# MainSch.net
KiCad netlist of a schematic drawn in Altium Designer
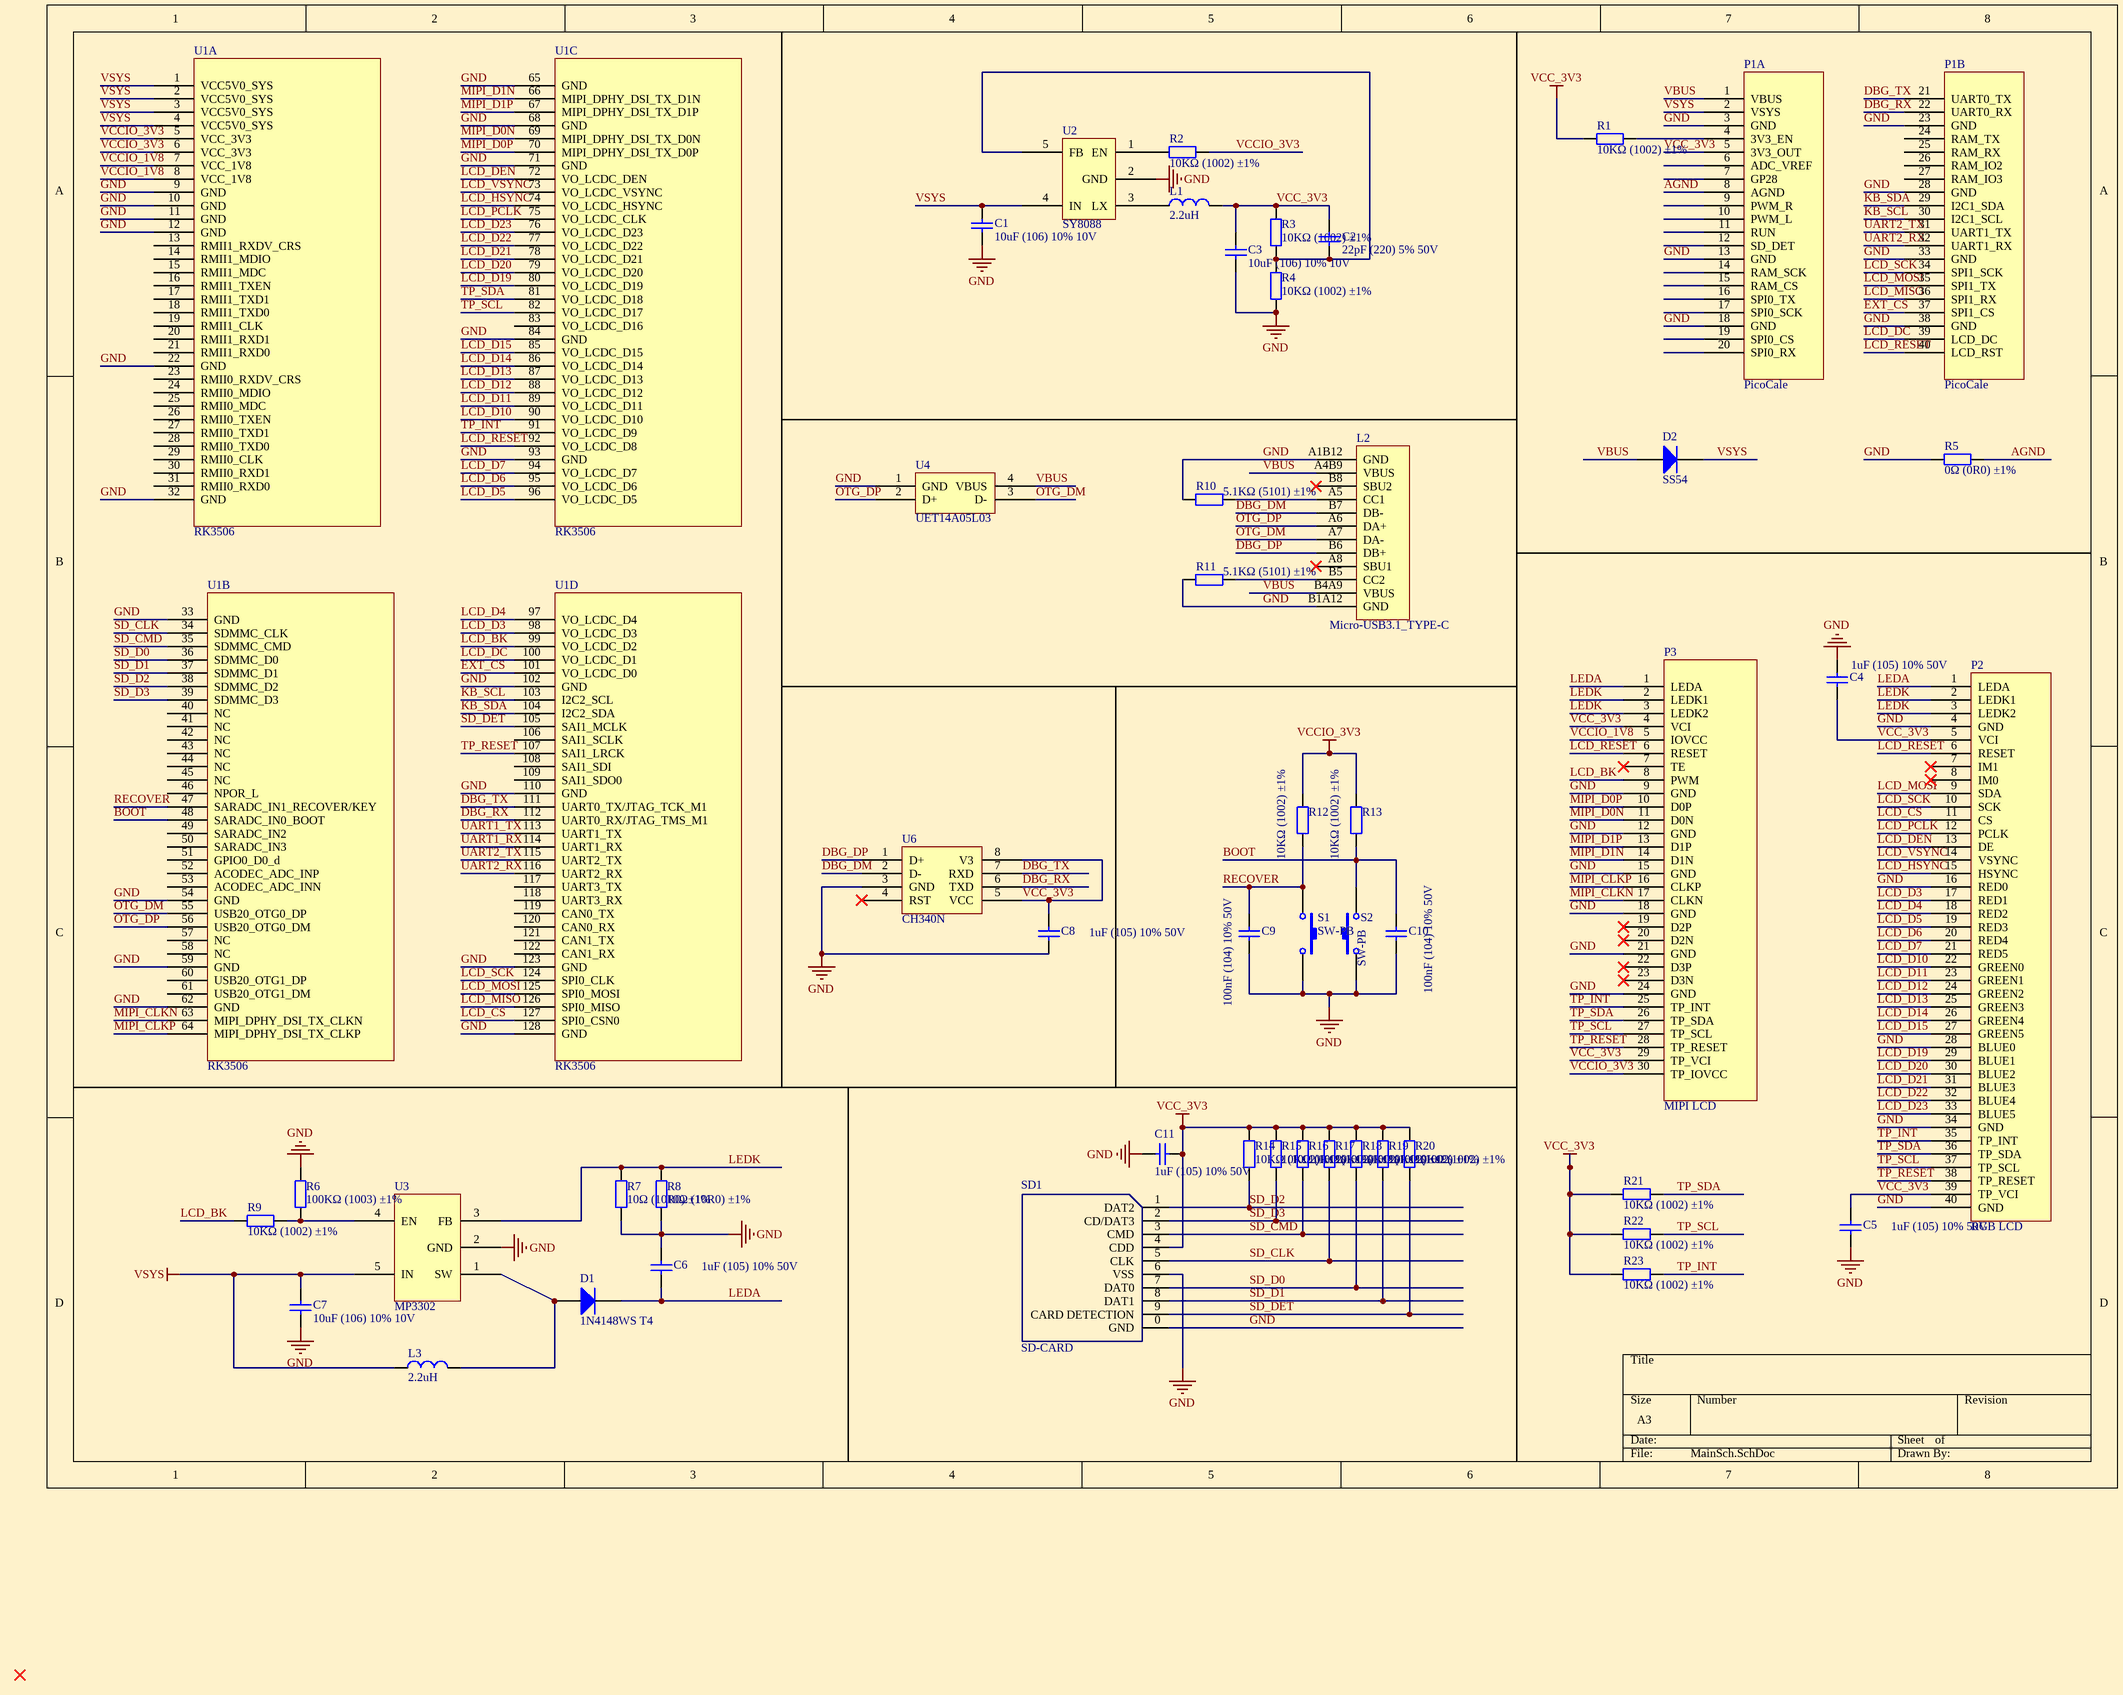
[diagram p0: MainSch.SchDoc]

(export (version "E")
  (design (tool "Eeschema 10.0.6"))
  (components
    (comp (ref "C1")
      (value "10uF (106) 10% 10V")
      (footprint "LC-0603_C")
      (description "贴片电容")
      (libsource (lib "Cap") (part "0603 10uF (106) 10% 10V"))
    )
    (comp (ref "C2")
      (value "22pF (220) 5% 50V")
      (footprint "LC-0603_C")
      (description "贴片电容")
      (libsource (lib "Cap") (part "0603 22pF (220) 5% 50V"))
    )
    (comp (ref "C3")
      (value "10uF (106) 10% 10V")
      (footprint "LC-0603_C")
      (description "贴片电容")
      (libsource (lib "Cap") (part "0603 10uF (106) 10% 10V"))
    )
    (comp (ref "C4")
      (value "1uF (105) 10% 50V")
      (footprint "LC-0603_C")
      (description "贴片电容")
      (libsource (lib "Cap") (part "0603 1uF (105) 10% 50V"))
    )
    (comp (ref "C5")
      (value "1uF (105) 10% 50V")
      (footprint "LC-0603_C")
      (description "贴片电容")
      (libsource (lib "Cap") (part "0603 1uF (105) 10% 50V"))
    )
    (comp (ref "C6")
      (value "1uF (105) 10% 50V")
      (footprint "LC-0603_C")
      (description "贴片电容")
      (libsource (lib "Cap") (part "0603 1uF (105) 10% 50V"))
    )
    (comp (ref "C7")
      (value "10uF (106) 10% 10V")
      (footprint "LC-0603_C")
      (description "贴片电容")
      (libsource (lib "Cap") (part "0603 10uF (106) 10% 10V"))
    )
    (comp (ref "C8")
      (value "1uF (105) 10% 50V")
      (footprint "LC-0603_C")
      (description "贴片电容")
      (libsource (lib "Cap") (part "0603 1uF (105) 10% 50V"))
    )
    (comp (ref "C9")
      (value "100nF (104) 10% 50V")
      (footprint "LC-0603_C")
      (description "贴片电容")
      (libsource (lib "Cap") (part "0603 100nF (104) 10% 50V"))
    )
    (comp (ref "C10")
      (value "100nF (104) 10% 50V")
      (footprint "LC-0603_C")
      (description "贴片电容")
      (libsource (lib "Cap") (part "0603 100nF (104) 10% 50V"))
    )
    (comp (ref "C11")
      (value "1uF (105) 10% 50V")
      (footprint "LC-0603_C")
      (description "贴片电容")
      (libsource (lib "Cap") (part "0603 1uF (105) 10% 50V"))
    )
    (comp (ref "D1")
      (value "1N4148WS T4")
      (footprint "LC-SOD-323")
      (description "二极管")
      (libsource (lib "Diode") (part "SOD-323 1N4148WS T4"))
    )
    (comp (ref "D2")
      (value "SS54")
      (footprint "LC-SMA(DO-214AC)_S1")
      (description "二极管")
      (libsource (lib "Diode") (part "SMA(DO-214AC) SS54"))
    )
    (comp (ref "L1")
      (value "2.2uH")
      (footprint "L-CD52")
      (description "电感")
      (libsource (lib "tony") (part "INDUCTOR"))
    )
    (comp (ref "L2")
      (value "Micro-USB3.1_TYPE-C")
      (footprint "USB_TypeC_SMD_16P")
      (libsource (lib "Miscellaneous Socket") (part "Micro-USB3.1_TYPE-C"))
    )
    (comp (ref "L3")
      (value "2.2uH")
      (footprint "L-CD52")
      (description "电感")
      (libsource (lib "tony") (part "INDUCTOR"))
    )
    (comp (ref "P1")
      (value "PicoCale")
      (footprint "Pico")
      (libsource (lib "rk3506_core") (part "PicoCale_Socket"))
    )
    (comp (ref "P2")
      (value "RGB LCD")
      (footprint "FPC0.5-40")
      (libsource (lib "rk3506_core") (part "RGB_40PIN"))
    )
    (comp (ref "P3")
      (value "MIPI LCD")
      (footprint "FPC0.5-30")
      (libsource (lib "rk3506_core") (part "MIPI_30P"))
    )
    (comp (ref "R1")
      (value "10KΩ (1002) ±1%")
      (footprint "LC-0603_R")
      (description "贴片电阻")
      (libsource (lib "") (part "0603 10KΩ (1002) 1%_2"))
    )
    (comp (ref "R2")
      (value "10KΩ (1002) ±1%")
      (footprint "LC-0603_R")
      (description "贴片电阻")
      (libsource (lib "") (part "0603 10KΩ (1002) 1%_2"))
    )
    (comp (ref "R3")
      (value "10KΩ (1002) ±1%")
      (footprint "LC-0603_R")
      (description "贴片电阻")
      (libsource (lib "RES") (part "0603 10KΩ (1002) 1%"))
    )
    (comp (ref "R4")
      (value "10KΩ (1002) ±1%")
      (footprint "LC-0603_R")
      (description "贴片电阻")
      (libsource (lib "RES") (part "0603 10KΩ (1002) 1%"))
    )
    (comp (ref "R5")
      (value "0Ω (0R0) ±1%")
      (footprint "LC-0603_R")
      (description "贴片电阻")
      (libsource (lib "RES") (part "0603 0Ω (0R0) 1%"))
    )
    (comp (ref "R6")
      (value "100KΩ (1003) ±1%")
      (footprint "LC-0603_R")
      (description "贴片电阻")
      (libsource (lib "RES") (part "0603 100KΩ (1003) 1%"))
    )
    (comp (ref "R7")
      (value "10Ω (10R0) ±1%")
      (footprint "LC-0603_R")
      (description "贴片电阻")
      (libsource (lib "RES") (part "0603 10Ω (10R0) 1%"))
    )
    (comp (ref "R8")
      (value "10Ω (10R0) ±1%")
      (footprint "LC-0603_R")
      (description "贴片电阻")
      (libsource (lib "RES") (part "0603 10Ω (10R0) 1%"))
    )
    (comp (ref "R9")
      (value "10KΩ (1002) ±1%")
      (footprint "LC-0603_R")
      (description "贴片电阻")
      (libsource (lib "") (part "0603 10KΩ (1002) 1%_2"))
    )
    (comp (ref "R10")
      (value "5.1KΩ (5101) ±1%")
      (footprint "LC-0603_R")
      (description "贴片电阻")
      (libsource (lib "RES") (part "0603 5.1KΩ (5101) 1%"))
    )
    (comp (ref "R11")
      (value "5.1KΩ (5101) ±1%")
      (footprint "LC-0603_R")
      (description "贴片电阻")
      (libsource (lib "RES") (part "0603 5.1KΩ (5101) 1%"))
    )
    (comp (ref "R12")
      (value "10KΩ (1002) ±1%")
      (footprint "LC-0603_R")
      (description "贴片电阻")
      (libsource (lib "RES") (part "0603 10KΩ (1002) 1%"))
    )
    (comp (ref "R13")
      (value "10KΩ (1002) ±1%")
      (footprint "LC-0603_R")
      (description "贴片电阻")
      (libsource (lib "RES") (part "0603 10KΩ (1002) 1%"))
    )
    (comp (ref "R14")
      (value "10KΩ (1002) ±1%")
      (footprint "LC-0603_R")
      (description "贴片电阻")
      (libsource (lib "RES") (part "0603 10KΩ (1002) 1%"))
    )
    (comp (ref "R15")
      (value "10KΩ (1002) ±1%")
      (footprint "LC-0603_R")
      (description "贴片电阻")
      (libsource (lib "RES") (part "0603 10KΩ (1002) 1%"))
    )
    (comp (ref "R16")
      (value "10KΩ (1002) ±1%")
      (footprint "LC-0603_R")
      (description "贴片电阻")
      (libsource (lib "RES") (part "0603 10KΩ (1002) 1%"))
    )
    (comp (ref "R17")
      (value "10KΩ (1002) ±1%")
      (footprint "LC-0603_R")
      (description "贴片电阻")
      (libsource (lib "RES") (part "0603 10KΩ (1002) 1%"))
    )
    (comp (ref "R18")
      (value "10KΩ (1002) ±1%")
      (footprint "LC-0603_R")
      (description "贴片电阻")
      (libsource (lib "RES") (part "0603 10KΩ (1002) 1%"))
    )
    (comp (ref "R19")
      (value "10KΩ (1002) ±1%")
      (footprint "LC-0603_R")
      (description "贴片电阻")
      (libsource (lib "RES") (part "0603 10KΩ (1002) 1%"))
    )
    (comp (ref "R20")
      (value "10KΩ (1002) ±1%")
      (footprint "LC-0603_R")
      (description "贴片电阻")
      (libsource (lib "RES") (part "0603 10KΩ (1002) 1%"))
    )
    (comp (ref "R21")
      (value "10KΩ (1002) ±1%")
      (footprint "LC-0603_R")
      (description "贴片电阻")
      (libsource (lib "") (part "0603 10KΩ (1002) 1%_1"))
    )
    (comp (ref "R22")
      (value "10KΩ (1002) ±1%")
      (footprint "LC-0603_R")
      (description "贴片电阻")
      (libsource (lib "") (part "0603 10KΩ (1002) 1%_1"))
    )
    (comp (ref "R23")
      (value "10KΩ (1002) ±1%")
      (footprint "LC-0603_R")
      (description "贴片电阻")
      (libsource (lib "") (part "0603 10KΩ (1002) 1%_1"))
    )
    (comp (ref "S1")
      (value "SW-PB")
      (footprint "TS-1030")
      (description "轻触开关")
      (fields (field (name "PUBLISHER") "Altium Limited"))
      (libsource (lib "tony") (part "SW-PB"))
    )
    (comp (ref "S2")
      (value "SW-PB")
      (footprint "TS-1030")
      (description "轻触开关")
      (fields (field (name "PUBLISHER") "Altium Limited"))
      (libsource (lib "tony") (part "SW-PB"))
    )
    (comp (ref "SD1")
      (value "SD-CARD")
      (footprint "SD-CARD-Micro")
      (libsource (lib "Miscellaneous Socket") (part "SD-CARD"))
    )
    (comp (ref "U1")
      (value "RK3506")
      (footprint "RK3506")
      (libsource (lib "rk3506_core") (part "RK3506G_CORE"))
    )
    (comp (ref "U2") (value "SY8088") (footprint "SOT23-5") (libsource (lib "rk3506_core") (part "SY8088")))
    (comp (ref "U3") (value "MP3302") (footprint "SOT23-5") (libsource (lib "rk3506_core") (part "MP3302")))
    (comp (ref "U4")
      (value "UET14A05L03")
      (footprint "SOT-143")
      (libsource (lib "rk3506_core") (part "UET14A05L03"))
    )
    (comp (ref "U6") (value "CH340N") (footprint "SOP8") (libsource (lib "rk3506_core") (part "CH340N")))
  )
  (nets
    (net (code "1") (name "/AGND") (class "Default")
      (node (ref "P1") (pin "8") (pinfunction "AGND_8") (pintype "passive"))
      (node (ref "R5") (pin "2") (pinfunction "2_2") (pintype "passive"))
    )
    (net (code "2") (name "/BOOT") (class "Default")
      (node (ref "C10") (pin "2") (pinfunction "2_2") (pintype "passive"))
      (node (ref "R13") (pin "1") (pinfunction "1_1") (pintype "passive"))
      (node (ref "S2") (pin "2") (pinfunction "2_2") (pintype "passive"))
      (node (ref "U1") (pin "48") (pinfunction "SARADC_IN0_BOOT_48") (pintype "passive"))
    )
    (net (code "3") (name "/DBG_DM") (class "Default")
      (node (ref "L2") (pin "B7") (pinfunction "DB-_B7") (pintype "passive"))
      (node (ref "U6") (pin "2") (pinfunction "D-_2") (pintype "passive"))
    )
    (net (code "4") (name "/DBG_DP") (class "Default")
      (node (ref "L2") (pin "B6") (pinfunction "DB+_B6") (pintype "passive"))
      (node (ref "U6") (pin "1") (pinfunction "D+_1") (pintype "passive"))
    )
    (net (code "5") (name "/DBG_RX") (class "Default")
      (node (ref "P1") (pin "22") (pinfunction "UART0_RX_22") (pintype "passive"))
      (node (ref "U1") (pin "112") (pinfunction "UART0_RX/JTAG_TMS_M1_112") (pintype "passive"))
      (node (ref "U6") (pin "6") (pinfunction "TXD_6") (pintype "passive"))
    )
    (net (code "6") (name "/DBG_TX") (class "Default")
      (node (ref "P1") (pin "21") (pinfunction "UART0_TX_21") (pintype "passive"))
      (node (ref "U1") (pin "111") (pinfunction "UART0_TX/JTAG_TCK_M1_111") (pintype "passive"))
      (node (ref "U6") (pin "7") (pinfunction "RXD_7") (pintype "passive"))
    )
    (net (code "7") (name "/EXT_CS") (class "Default")
      (node (ref "P1") (pin "37") (pinfunction "SPI1_CS_37") (pintype "passive"))
      (node (ref "U1") (pin "101") (pinfunction "VO_LCDC_D0_101") (pintype "passive"))
    )
    (net (code "8") (name "/KB_SCL") (class "Default")
      (node (ref "P1") (pin "30") (pinfunction "I2C1_SCL_30") (pintype "passive"))
      (node (ref "U1") (pin "103") (pinfunction "I2C2_SCL_103") (pintype "passive"))
    )
    (net (code "9") (name "/KB_SDA") (class "Default")
      (node (ref "P1") (pin "29") (pinfunction "I2C1_SDA_29") (pintype "passive"))
      (node (ref "U1") (pin "104") (pinfunction "I2C2_SDA_104") (pintype "passive"))
    )
    (net (code "10") (name "/LCD_BK") (class "Default")
      (node (ref "P3") (pin "8") (pinfunction "PWM_8") (pintype "passive"))
      (node (ref "R9") (pin "1") (pinfunction "1_1") (pintype "passive"))
      (node (ref "U1") (pin "99") (pinfunction "VO_LCDC_D2_99") (pintype "passive"))
    )
    (net (code "11") (name "/LCD_CS") (class "Default")
      (node (ref "P2") (pin "11") (pinfunction "CS_11") (pintype "passive"))
      (node (ref "U1") (pin "127") (pinfunction "SPI0_CSN0_127") (pintype "passive"))
    )
    (net (code "12") (name "/LCD_D3") (class "Default")
      (node (ref "P2") (pin "17") (pinfunction "RED1_17") (pintype "passive"))
      (node (ref "U1") (pin "98") (pinfunction "VO_LCDC_D3_98") (pintype "passive"))
    )
    (net (code "13") (name "/LCD_D4") (class "Default")
      (node (ref "P2") (pin "18") (pinfunction "RED2_18") (pintype "passive"))
      (node (ref "U1") (pin "97") (pinfunction "VO_LCDC_D4_97") (pintype "passive"))
    )
    (net (code "14") (name "/LCD_D5") (class "Default")
      (node (ref "P2") (pin "19") (pinfunction "RED3_19") (pintype "passive"))
      (node (ref "U1") (pin "96") (pinfunction "VO_LCDC_D5_96") (pintype "passive"))
    )
    (net (code "15") (name "/LCD_D6") (class "Default")
      (node (ref "P2") (pin "20") (pinfunction "RED4_20") (pintype "passive"))
      (node (ref "U1") (pin "95") (pinfunction "VO_LCDC_D6_95") (pintype "passive"))
    )
    (net (code "16") (name "/LCD_D7") (class "Default")
      (node (ref "P2") (pin "21") (pinfunction "RED5_21") (pintype "passive"))
      (node (ref "U1") (pin "94") (pinfunction "VO_LCDC_D7_94") (pintype "passive"))
    )
    (net (code "17") (name "/LCD_D10") (class "Default")
      (node (ref "P2") (pin "22") (pinfunction "GREEN0_22") (pintype "passive"))
      (node (ref "U1") (pin "90") (pinfunction "VO_LCDC_D10_90") (pintype "passive"))
    )
    (net (code "18") (name "/LCD_D11") (class "Default")
      (node (ref "P2") (pin "23") (pinfunction "GREEN1_23") (pintype "passive"))
      (node (ref "U1") (pin "89") (pinfunction "VO_LCDC_D11_89") (pintype "passive"))
    )
    (net (code "19") (name "/LCD_D12") (class "Default")
      (node (ref "P2") (pin "24") (pinfunction "GREEN2_24") (pintype "passive"))
      (node (ref "U1") (pin "88") (pinfunction "VO_LCDC_D12_88") (pintype "passive"))
    )
    (net (code "20") (name "/LCD_D13") (class "Default")
      (node (ref "P2") (pin "25") (pinfunction "GREEN3_25") (pintype "passive"))
      (node (ref "U1") (pin "87") (pinfunction "VO_LCDC_D13_87") (pintype "passive"))
    )
    (net (code "21") (name "/LCD_D14") (class "Default")
      (node (ref "P2") (pin "26") (pinfunction "GREEN4_26") (pintype "passive"))
      (node (ref "U1") (pin "86") (pinfunction "VO_LCDC_D14_86") (pintype "passive"))
    )
    (net (code "22") (name "/LCD_D15") (class "Default")
      (node (ref "P2") (pin "27") (pinfunction "GREEN5_27") (pintype "passive"))
      (node (ref "U1") (pin "85") (pinfunction "VO_LCDC_D15_85") (pintype "passive"))
    )
    (net (code "23") (name "/LCD_D19") (class "Default")
      (node (ref "P2") (pin "29") (pinfunction "BLUE1_29") (pintype "passive"))
      (node (ref "U1") (pin "80") (pinfunction "VO_LCDC_D19_80") (pintype "passive"))
    )
    (net (code "24") (name "/LCD_D20") (class "Default")
      (node (ref "P2") (pin "30") (pinfunction "BLUE2_30") (pintype "passive"))
      (node (ref "U1") (pin "79") (pinfunction "VO_LCDC_D20_79") (pintype "passive"))
    )
    (net (code "25") (name "/LCD_D21") (class "Default")
      (node (ref "P2") (pin "31") (pinfunction "BLUE3_31") (pintype "passive"))
      (node (ref "U1") (pin "78") (pinfunction "VO_LCDC_D21_78") (pintype "passive"))
    )
    (net (code "26") (name "/LCD_D22") (class "Default")
      (node (ref "P2") (pin "32") (pinfunction "BLUE4_32") (pintype "passive"))
      (node (ref "U1") (pin "77") (pinfunction "VO_LCDC_D22_77") (pintype "passive"))
    )
    (net (code "27") (name "/LCD_D23") (class "Default")
      (node (ref "P2") (pin "33") (pinfunction "BLUE5_33") (pintype "passive"))
      (node (ref "U1") (pin "76") (pinfunction "VO_LCDC_D23_76") (pintype "passive"))
    )
    (net (code "28") (name "/LCD_DC") (class "Default")
      (node (ref "P1") (pin "39") (pinfunction "LCD_DC_39") (pintype "passive"))
      (node (ref "U1") (pin "100") (pinfunction "VO_LCDC_D1_100") (pintype "passive"))
    )
    (net (code "29") (name "/LCD_DEN") (class "Default")
      (node (ref "P2") (pin "13") (pinfunction "DE_13") (pintype "passive"))
      (node (ref "U1") (pin "72") (pinfunction "VO_LCDC_DEN_72") (pintype "passive"))
    )
    (net (code "30") (name "/LCD_HSYNC") (class "Default")
      (node (ref "P2") (pin "15") (pinfunction "HSYNC_15") (pintype "passive"))
      (node (ref "U1") (pin "74") (pinfunction "VO_LCDC_HSYNC_74") (pintype "passive"))
    )
    (net (code "31") (name "/LCD_MISO") (class "Default")
      (node (ref "P1") (pin "36") (pinfunction "SPI1_RX_36") (pintype "passive"))
      (node (ref "U1") (pin "126") (pinfunction "SPI0_MISO_126") (pintype "passive"))
    )
    (net (code "32") (name "/LCD_MOSI") (class "Default")
      (node (ref "P1") (pin "35") (pinfunction "SPI1_TX_35") (pintype "passive"))
      (node (ref "P2") (pin "9") (pinfunction "SDA_9") (pintype "passive"))
      (node (ref "U1") (pin "125") (pinfunction "SPI0_MOSI_125") (pintype "passive"))
    )
    (net (code "33") (name "/LCD_PCLK") (class "Default")
      (node (ref "P2") (pin "12") (pinfunction "PCLK_12") (pintype "passive"))
      (node (ref "U1") (pin "75") (pinfunction "VO_LCDC_CLK_75") (pintype "passive"))
    )
    (net (code "34") (name "/LCD_RESET") (class "Default")
      (node (ref "P1") (pin "40") (pinfunction "LCD_RST_40") (pintype "passive"))
      (node (ref "P2") (pin "6") (pinfunction "RESET_6") (pintype "passive"))
      (node (ref "P3") (pin "6") (pinfunction "RESET_6") (pintype "passive"))
      (node (ref "U1") (pin "92") (pinfunction "VO_LCDC_D8_92") (pintype "passive"))
    )
    (net (code "35") (name "/LCD_SCK") (class "Default")
      (node (ref "P1") (pin "34") (pinfunction "SPI1_SCK_34") (pintype "passive"))
      (node (ref "P2") (pin "10") (pinfunction "SCK_10") (pintype "passive"))
      (node (ref "U1") (pin "124") (pinfunction "SPI0_CLK_124") (pintype "passive"))
    )
    (net (code "36") (name "/LCD_VSYNC") (class "Default")
      (node (ref "P2") (pin "14") (pinfunction "VSYNC_14") (pintype "passive"))
      (node (ref "U1") (pin "73") (pinfunction "VO_LCDC_VSYNC_73") (pintype "passive"))
    )
    (net (code "37") (name "/LEDA") (class "Default")
      (node (ref "C6") (pin "1") (pinfunction "1_1") (pintype "passive"))
      (node (ref "D1") (pin "2") (pinfunction "K_2") (pintype "passive"))
      (node (ref "P2") (pin "1") (pinfunction "LEDA_1") (pintype "passive"))
      (node (ref "P3") (pin "1") (pinfunction "LEDA_1") (pintype "passive"))
    )
    (net (code "38") (name "/LEDK") (class "Default")
      (node (ref "P2") (pin "2") (pinfunction "LEDK1_2") (pintype "passive"))
      (node (ref "P2") (pin "3") (pinfunction "LEDK2_3") (pintype "passive"))
      (node (ref "P3") (pin "2") (pinfunction "LEDK1_2") (pintype "passive"))
      (node (ref "P3") (pin "3") (pinfunction "LEDK2_3") (pintype "passive"))
      (node (ref "R7") (pin "2") (pinfunction "2_2") (pintype "passive"))
      (node (ref "R8") (pin "2") (pinfunction "2_2") (pintype "passive"))
      (node (ref "U3") (pin "3") (pinfunction "FB_3") (pintype "passive"))
    )
    (net (code "39") (name "/MIPI_CLKN") (class "Default")
      (node (ref "P3") (pin "17") (pinfunction "CLKN_17") (pintype "passive"))
      (node (ref "U1") (pin "63") (pinfunction "MIPI_DPHY_DSI_TX_CLKN_63") (pintype "passive"))
    )
    (net (code "40") (name "/MIPI_CLKP") (class "Default")
      (node (ref "P3") (pin "16") (pinfunction "CLKP_16") (pintype "passive"))
      (node (ref "U1") (pin "64") (pinfunction "MIPI_DPHY_DSI_TX_CLKP_64") (pintype "passive"))
    )
    (net (code "41") (name "/MIPI_D0N") (class "Default")
      (node (ref "P3") (pin "11") (pinfunction "D0N_11") (pintype "passive"))
      (node (ref "U1") (pin "69") (pinfunction "MIPI_DPHY_DSI_TX_D0N_69") (pintype "passive"))
    )
    (net (code "42") (name "/MIPI_D0P") (class "Default")
      (node (ref "P3") (pin "10") (pinfunction "D0P_10") (pintype "passive"))
      (node (ref "U1") (pin "70") (pinfunction "MIPI_DPHY_DSI_TX_D0P_70") (pintype "passive"))
    )
    (net (code "43") (name "/MIPI_D1N") (class "Default")
      (node (ref "P3") (pin "14") (pinfunction "D1N_14") (pintype "passive"))
      (node (ref "U1") (pin "66") (pinfunction "MIPI_DPHY_DSI_TX_D1N_66") (pintype "passive"))
    )
    (net (code "44") (name "/MIPI_D1P") (class "Default")
      (node (ref "P3") (pin "13") (pinfunction "D1P_13") (pintype "passive"))
      (node (ref "U1") (pin "67") (pinfunction "MIPI_DPHY_DSI_TX_D1P_67") (pintype "passive"))
    )
    (net (code "45") (name "/OTG_DM") (class "Default")
      (node (ref "L2") (pin "A7") (pinfunction "DA-_A7") (pintype "passive"))
      (node (ref "U1") (pin "55") (pinfunction "USB20_OTG0_DP_55") (pintype "passive"))
      (node (ref "U4") (pin "3") (pinfunction "D-_3") (pintype "passive"))
    )
    (net (code "46") (name "/OTG_DP") (class "Default")
      (node (ref "L2") (pin "A6") (pinfunction "DA+_A6") (pintype "passive"))
      (node (ref "U1") (pin "56") (pinfunction "USB20_OTG0_DM_56") (pintype "passive"))
      (node (ref "U4") (pin "2") (pinfunction "D+_2") (pintype "passive"))
    )
    (net (code "47") (name "/RECOVER") (class "Default")
      (node (ref "C9") (pin "2") (pinfunction "2_2") (pintype "passive"))
      (node (ref "R12") (pin "1") (pinfunction "1_1") (pintype "passive"))
      (node (ref "S1") (pin "1") (pinfunction "1_1") (pintype "passive"))
      (node (ref "U1") (pin "47") (pinfunction "SARADC_IN1_RECOVER/KEY_47") (pintype "passive"))
    )
    (net (code "48") (name "/SD_CLK") (class "Default")
      (node (ref "R17") (pin "1") (pinfunction "1_1") (pintype "passive"))
      (node (ref "SD1") (pin "5") (pinfunction "CLK_5") (pintype "passive"))
      (node (ref "U1") (pin "34") (pinfunction "SDMMC_CLK_34") (pintype "passive"))
    )
    (net (code "49") (name "/SD_CMD") (class "Default")
      (node (ref "R16") (pin "1") (pinfunction "1_1") (pintype "passive"))
      (node (ref "SD1") (pin "3") (pinfunction "CMD_3") (pintype "passive"))
      (node (ref "U1") (pin "35") (pinfunction "SDMMC_CMD_35") (pintype "passive"))
    )
    (net (code "50") (name "/SD_D0") (class "Default")
      (node (ref "R18") (pin "1") (pinfunction "1_1") (pintype "passive"))
      (node (ref "SD1") (pin "7") (pinfunction "DAT0_7") (pintype "passive"))
      (node (ref "U1") (pin "36") (pinfunction "SDMMC_D0_36") (pintype "passive"))
    )
    (net (code "51") (name "/SD_D1") (class "Default")
      (node (ref "R19") (pin "1") (pinfunction "1_1") (pintype "passive"))
      (node (ref "SD1") (pin "8") (pinfunction "DAT1_8") (pintype "passive"))
      (node (ref "U1") (pin "37") (pinfunction "SDMMC_D1_37") (pintype "passive"))
    )
    (net (code "52") (name "/SD_D2") (class "Default")
      (node (ref "R14") (pin "1") (pinfunction "1_1") (pintype "passive"))
      (node (ref "SD1") (pin "1") (pinfunction "DAT2_1") (pintype "passive"))
      (node (ref "U1") (pin "38") (pinfunction "SDMMC_D2_38") (pintype "passive"))
    )
    (net (code "53") (name "/SD_D3") (class "Default")
      (node (ref "R15") (pin "1") (pinfunction "1_1") (pintype "passive"))
      (node (ref "SD1") (pin "2") (pinfunction "CD/DAT3_2") (pintype "passive"))
      (node (ref "U1") (pin "39") (pinfunction "SDMMC_D3_39") (pintype "passive"))
    )
    (net (code "54") (name "/SD_DET") (class "Default")
      (node (ref "R20") (pin "1") (pinfunction "1_1") (pintype "passive"))
      (node (ref "SD1") (pin "9") (pinfunction "CARD_DETECTION_9") (pintype "passive"))
      (node (ref "U1") (pin "105") (pinfunction "SAI1_MCLK_105") (pintype "passive"))
    )
    (net (code "55") (name "/TP_INT") (class "Default")
      (node (ref "P2") (pin "35") (pinfunction "TP_INT_35") (pintype "passive"))
      (node (ref "P3") (pin "25") (pinfunction "TP_INT_25") (pintype "passive"))
      (node (ref "R23") (pin "1") (pinfunction "1_1") (pintype "passive"))
      (node (ref "U1") (pin "91") (pinfunction "VO_LCDC_D9_91") (pintype "passive"))
    )
    (net (code "56") (name "/TP_RESET") (class "Default")
      (node (ref "P2") (pin "38") (pinfunction "TP_RESET_38") (pintype "passive"))
      (node (ref "P3") (pin "28") (pinfunction "TP_RESET_28") (pintype "passive"))
      (node (ref "U1") (pin "107") (pinfunction "SAI1_LRCK_107") (pintype "passive"))
    )
    (net (code "57") (name "/TP_SCL") (class "Default")
      (node (ref "P2") (pin "37") (pinfunction "TP_SCL_37") (pintype "passive"))
      (node (ref "P3") (pin "27") (pinfunction "TP_SCL_27") (pintype "passive"))
      (node (ref "R22") (pin "1") (pinfunction "1_1") (pintype "passive"))
      (node (ref "U1") (pin "82") (pinfunction "VO_LCDC_D17_82") (pintype "passive"))
    )
    (net (code "58") (name "/TP_SDA") (class "Default")
      (node (ref "P2") (pin "36") (pinfunction "TP_SDA_36") (pintype "passive"))
      (node (ref "P3") (pin "26") (pinfunction "TP_SDA_26") (pintype "passive"))
      (node (ref "R21") (pin "1") (pinfunction "1_1") (pintype "passive"))
      (node (ref "U1") (pin "81") (pinfunction "VO_LCDC_D18_81") (pintype "passive"))
    )
    (net (code "59") (name "/UART1_RX") (class "Default")
      (node (ref "U1") (pin "114") (pinfunction "UART1_RX_114") (pintype "passive"))
    )
    (net (code "60") (name "/UART1_TX") (class "Default")
      (node (ref "U1") (pin "113") (pinfunction "UART1_TX_113") (pintype "passive"))
    )
    (net (code "61") (name "/UART2_RX") (class "Default")
      (node (ref "P1") (pin "32") (pinfunction "UART1_RX_32") (pintype "passive"))
      (node (ref "U1") (pin "116") (pinfunction "UART2_RX_116") (pintype "passive"))
    )
    (net (code "62") (name "/UART2_TX") (class "Default")
      (node (ref "P1") (pin "31") (pinfunction "UART1_TX_31") (pintype "passive"))
      (node (ref "U1") (pin "115") (pinfunction "UART2_TX_115") (pintype "passive"))
    )
    (net (code "63") (name "/VBUS") (class "Default")
      (node (ref "D2") (pin "1") (pinfunction "A_1") (pintype "passive"))
      (node (ref "L2") (pin "A4B9") (pinfunction "VBUS_A4B9") (pintype "passive"))
      (node (ref "L2") (pin "B4A9") (pinfunction "VBUS_B4A9") (pintype "passive"))
      (node (ref "P1") (pin "1") (pinfunction "VBUS_1") (pintype "passive"))
      (node (ref "U4") (pin "4") (pinfunction "VBUS_4") (pintype "passive"))
    )
    (net (code "64") (name "/VCCIO_1V8") (class "Default")
      (node (ref "P3") (pin "5") (pinfunction "IOVCC_5") (pintype "passive"))
      (node (ref "U1") (pin "7") (pinfunction "VCC_1V8_7") (pintype "passive"))
      (node (ref "U1") (pin "8") (pinfunction "VCC_1V8_8") (pintype "passive"))
    )
    (net (code "65") (name "GND") (class "Default")
      (node (ref "C1") (pin "1") (pinfunction "1_1") (pintype "passive"))
      (node (ref "C10") (pin "1") (pinfunction "1_1") (pintype "passive"))
      (node (ref "C11") (pin "2") (pinfunction "2_2") (pintype "passive"))
      (node (ref "C3") (pin "1") (pinfunction "1_1") (pintype "passive"))
      (node (ref "C4") (pin "1") (pinfunction "1_1") (pintype "passive"))
      (node (ref "C5") (pin "1") (pinfunction "1_1") (pintype "passive"))
      (node (ref "C6") (pin "2") (pinfunction "2_2") (pintype "passive"))
      (node (ref "C7") (pin "1") (pinfunction "1_1") (pintype "passive"))
      (node (ref "C8") (pin "1") (pinfunction "1_1") (pintype "passive"))
      (node (ref "C9") (pin "1") (pinfunction "1_1") (pintype "passive"))
      (node (ref "L2") (pin "A1B12") (pinfunction "GND_A1B12") (pintype "passive"))
      (node (ref "L2") (pin "B1A12") (pinfunction "GND_B1A12") (pintype "passive"))
      (node (ref "P1") (pin "13") (pinfunction "GND_13") (pintype "passive"))
      (node (ref "P1") (pin "18") (pinfunction "GND_18") (pintype "passive"))
      (node (ref "P1") (pin "23") (pinfunction "GND_23") (pintype "passive"))
      (node (ref "P1") (pin "28") (pinfunction "GND_28") (pintype "passive"))
      (node (ref "P1") (pin "3") (pinfunction "GND_3") (pintype "passive"))
      (node (ref "P1") (pin "33") (pinfunction "GND_33") (pintype "passive"))
      (node (ref "P1") (pin "38") (pinfunction "GND_38") (pintype "passive"))
      (node (ref "P2") (pin "16") (pinfunction "RED0_16") (pintype "passive"))
      (node (ref "P2") (pin "28") (pinfunction "BLUE0_28") (pintype "passive"))
      (node (ref "P2") (pin "34") (pinfunction "GND_34") (pintype "passive"))
      (node (ref "P2") (pin "4") (pinfunction "GND_4") (pintype "passive"))
      (node (ref "P2") (pin "40") (pinfunction "GND_40") (pintype "passive"))
      (node (ref "P3") (pin "12") (pinfunction "GND_12") (pintype "passive"))
      (node (ref "P3") (pin "15") (pinfunction "GND_15") (pintype "passive"))
      (node (ref "P3") (pin "18") (pinfunction "GND_18") (pintype "passive"))
      (node (ref "P3") (pin "21") (pinfunction "GND_21") (pintype "passive"))
      (node (ref "P3") (pin "24") (pinfunction "GND_24") (pintype "passive"))
      (node (ref "P3") (pin "9") (pinfunction "GND_9") (pintype "passive"))
      (node (ref "R10") (pin "1") (pinfunction "1_1") (pintype "passive"))
      (node (ref "R11") (pin "1") (pinfunction "1_1") (pintype "passive"))
      (node (ref "R4") (pin "1") (pinfunction "1_1") (pintype "passive"))
      (node (ref "R5") (pin "1") (pinfunction "1_1") (pintype "passive"))
      (node (ref "R6") (pin "2") (pinfunction "2_2") (pintype "passive"))
      (node (ref "R7") (pin "1") (pinfunction "1_1") (pintype "passive"))
      (node (ref "R8") (pin "1") (pinfunction "1_1") (pintype "passive"))
      (node (ref "S1") (pin "2") (pinfunction "2_2") (pintype "passive"))
      (node (ref "S2") (pin "1") (pinfunction "1_1") (pintype "passive"))
      (node (ref "SD1") (pin "0") (pinfunction "GND_0") (pintype "passive"))
      (node (ref "SD1") (pin "6") (pinfunction "VSS_6") (pintype "passive"))
      (node (ref "U1") (pin "10") (pinfunction "GND_10") (pintype "passive"))
      (node (ref "U1") (pin "102") (pinfunction "GND_102") (pintype "passive"))
      (node (ref "U1") (pin "11") (pinfunction "GND_11") (pintype "passive"))
      (node (ref "U1") (pin "110") (pinfunction "GND_110") (pintype "passive"))
      (node (ref "U1") (pin "12") (pinfunction "GND_12") (pintype "passive"))
      (node (ref "U1") (pin "123") (pinfunction "GND_123") (pintype "passive"))
      (node (ref "U1") (pin "128") (pinfunction "GND_128") (pintype "passive"))
      (node (ref "U1") (pin "22") (pinfunction "GND_22") (pintype "passive"))
      (node (ref "U1") (pin "32") (pinfunction "GND_32") (pintype "passive"))
      (node (ref "U1") (pin "33") (pinfunction "GND_33") (pintype "passive"))
      (node (ref "U1") (pin "54") (pinfunction "GND_54") (pintype "passive"))
      (node (ref "U1") (pin "59") (pinfunction "GND_59") (pintype "passive"))
      (node (ref "U1") (pin "62") (pinfunction "GND_62") (pintype "passive"))
      (node (ref "U1") (pin "65") (pinfunction "GND_65") (pintype "passive"))
      (node (ref "U1") (pin "68") (pinfunction "GND_68") (pintype "passive"))
      (node (ref "U1") (pin "71") (pinfunction "GND_71") (pintype "passive"))
      (node (ref "U1") (pin "84") (pinfunction "GND_84") (pintype "passive"))
      (node (ref "U1") (pin "9") (pinfunction "GND_9") (pintype "passive"))
      (node (ref "U1") (pin "93") (pinfunction "GND_93") (pintype "passive"))
      (node (ref "U2") (pin "2") (pinfunction "GND_2") (pintype "passive"))
      (node (ref "U3") (pin "2") (pinfunction "GND_2") (pintype "passive"))
      (node (ref "U4") (pin "1") (pinfunction "GND_1") (pintype "passive"))
      (node (ref "U6") (pin "3") (pinfunction "GND_3") (pintype "passive"))
    )
    (net (code "66") (name "Net-(D1-A)") (class "Default")
      (node (ref "D1") (pin "1") (pinfunction "A_1") (pintype "passive"))
      (node (ref "L3") (pin "1") (pinfunction "1_1") (pintype "passive"))
      (node (ref "U3") (pin "1") (pinfunction "SW_1") (pintype "passive"))
    )
    (net (code "67") (name "Net-(L2-CC1)") (class "Default")
      (node (ref "L2") (pin "A5") (pinfunction "CC1_A5") (pintype "passive"))
      (node (ref "R10") (pin "2") (pinfunction "2_2") (pintype "passive"))
    )
    (net (code "68") (name "Net-(L2-CC2)") (class "Default")
      (node (ref "L2") (pin "B5") (pinfunction "CC2_B5") (pintype "passive"))
      (node (ref "R11") (pin "2") (pinfunction "2_2") (pintype "passive"))
    )
    (net (code "69") (name "Net-(P1A-3V3_EN)") (class "Default")
      (node (ref "P1") (pin "4") (pinfunction "3V3_EN_4") (pintype "passive"))
      (node (ref "R1") (pin "2") (pinfunction "2_2") (pintype "passive"))
    )
    (net (code "70") (name "Net-(U2-EN)") (class "Default")
      (node (ref "R2") (pin "1") (pinfunction "1_1") (pintype "passive"))
      (node (ref "U2") (pin "1") (pinfunction "EN_1") (pintype "passive"))
    )
    (net (code "71") (name "Net-(U2-FB)") (class "Default")
      (node (ref "C2") (pin "1") (pinfunction "1_1") (pintype "passive"))
      (node (ref "R3") (pin "1") (pinfunction "1_1") (pintype "passive"))
      (node (ref "R4") (pin "2") (pinfunction "2_2") (pintype "passive"))
      (node (ref "U2") (pin "5") (pinfunction "FB_5") (pintype "passive"))
    )
    (net (code "72") (name "Net-(U2-LX)") (class "Default")
      (node (ref "L1") (pin "2") (pinfunction "2_2") (pintype "passive"))
      (node (ref "U2") (pin "3") (pinfunction "LX_3") (pintype "passive"))
    )
    (net (code "73") (name "Net-(U3-EN)") (class "Default")
      (node (ref "R6") (pin "1") (pinfunction "1_1") (pintype "passive"))
      (node (ref "R9") (pin "2") (pinfunction "2_2") (pintype "passive"))
      (node (ref "U3") (pin "4") (pinfunction "EN_4") (pintype "passive"))
    )
    (net (code "74") (name "VCCIO_3V3") (class "Default")
      (node (ref "P3") (pin "30") (pinfunction "TP_IOVCC_30") (pintype "passive"))
      (node (ref "R12") (pin "2") (pinfunction "2_2") (pintype "passive"))
      (node (ref "R13") (pin "2") (pinfunction "2_2") (pintype "passive"))
      (node (ref "R2") (pin "2") (pinfunction "2_2") (pintype "passive"))
      (node (ref "U1") (pin "5") (pinfunction "VCC_3V3_5") (pintype "passive"))
      (node (ref "U1") (pin "6") (pinfunction "VCC_3V3_6") (pintype "passive"))
    )
    (net (code "75") (name "VCC_3V3") (class "Default")
      (node (ref "C11") (pin "1") (pinfunction "1_1") (pintype "passive"))
      (node (ref "C2") (pin "2") (pinfunction "2_2") (pintype "passive"))
      (node (ref "C3") (pin "2") (pinfunction "2_2") (pintype "passive"))
      (node (ref "C4") (pin "2") (pinfunction "2_2") (pintype "passive"))
      (node (ref "C5") (pin "2") (pinfunction "2_2") (pintype "passive"))
      (node (ref "C8") (pin "2") (pinfunction "2_2") (pintype "passive"))
      (node (ref "L1") (pin "1") (pinfunction "1_1") (pintype "passive"))
      (node (ref "P1") (pin "5") (pinfunction "3V3_OUT_5") (pintype "passive"))
      (node (ref "P2") (pin "39") (pinfunction "TP_VCI_39") (pintype "passive"))
      (node (ref "P2") (pin "5") (pinfunction "VCI_5") (pintype "passive"))
      (node (ref "P3") (pin "29") (pinfunction "TP_VCI_29") (pintype "passive"))
      (node (ref "P3") (pin "4") (pinfunction "VCI_4") (pintype "passive"))
      (node (ref "R1") (pin "1") (pinfunction "1_1") (pintype "passive"))
      (node (ref "R14") (pin "2") (pinfunction "2_2") (pintype "passive"))
      (node (ref "R15") (pin "2") (pinfunction "2_2") (pintype "passive"))
      (node (ref "R16") (pin "2") (pinfunction "2_2") (pintype "passive"))
      (node (ref "R17") (pin "2") (pinfunction "2_2") (pintype "passive"))
      (node (ref "R18") (pin "2") (pinfunction "2_2") (pintype "passive"))
      (node (ref "R19") (pin "2") (pinfunction "2_2") (pintype "passive"))
      (node (ref "R20") (pin "2") (pinfunction "2_2") (pintype "passive"))
      (node (ref "R21") (pin "2") (pinfunction "2_2") (pintype "passive"))
      (node (ref "R22") (pin "2") (pinfunction "2_2") (pintype "passive"))
      (node (ref "R23") (pin "2") (pinfunction "2_2") (pintype "passive"))
      (node (ref "R3") (pin "2") (pinfunction "2_2") (pintype "passive"))
      (node (ref "SD1") (pin "4") (pinfunction "CDD_4") (pintype "passive"))
      (node (ref "U6") (pin "5") (pinfunction "VCC_5") (pintype "passive"))
      (node (ref "U6") (pin "8") (pinfunction "V3_8") (pintype "passive"))
    )
    (net (code "76") (name "VSYS") (class "Default")
      (node (ref "C1") (pin "2") (pinfunction "2_2") (pintype "passive"))
      (node (ref "C7") (pin "2") (pinfunction "2_2") (pintype "passive"))
      (node (ref "D2") (pin "2") (pinfunction "K_2") (pintype "passive"))
      (node (ref "L3") (pin "2") (pinfunction "2_2") (pintype "passive"))
      (node (ref "P1") (pin "2") (pinfunction "VSYS_2") (pintype "passive"))
      (node (ref "U1") (pin "1") (pinfunction "VCC5V0_SYS_1") (pintype "passive"))
      (node (ref "U1") (pin "2") (pinfunction "VCC5V0_SYS_2") (pintype "passive"))
      (node (ref "U1") (pin "3") (pinfunction "VCC5V0_SYS_3") (pintype "passive"))
      (node (ref "U1") (pin "4") (pinfunction "VCC5V0_SYS_4") (pintype "passive"))
      (node (ref "U2") (pin "4") (pinfunction "IN_4") (pintype "passive"))
      (node (ref "U3") (pin "5") (pinfunction "IN_5") (pintype "passive"))
    )
    (net (code "77") (name "unconnected-(L2-SBU1-PadA8)") (class "Default")
      (node (ref "L2") (pin "A8") (pinfunction "SBU1_A8") (pintype "passive+no_connect"))
    )
    (net (code "78") (name "unconnected-(L2-SBU2-PadB8)") (class "Default")
      (node (ref "L2") (pin "B8") (pinfunction "SBU2_B8") (pintype "passive+no_connect"))
    )
    (net (code "79") (name "unconnected-(P1A-ADC_VREF-Pad6)") (class "Default")
      (node (ref "P1") (pin "6") (pinfunction "ADC_VREF_6") (pintype "passive"))
    )
    (net (code "80") (name "unconnected-(P1A-GP28-Pad7)") (class "Default")
      (node (ref "P1") (pin "7") (pinfunction "GP28_7") (pintype "passive"))
    )
    (net (code "81") (name "unconnected-(P1A-PWM_L-Pad10)") (class "Default")
      (node (ref "P1") (pin "10") (pinfunction "PWM_L_10") (pintype "passive"))
    )
    (net (code "82") (name "unconnected-(P1A-PWM_R-Pad9)") (class "Default")
      (node (ref "P1") (pin "9") (pinfunction "PWM_R_9") (pintype "passive"))
    )
    (net (code "83") (name "unconnected-(P1A-RAM_CS-Pad15)") (class "Default")
      (node (ref "P1") (pin "15") (pinfunction "RAM_CS_15") (pintype "passive"))
    )
    (net (code "84") (name "unconnected-(P1A-RAM_SCK-Pad14)") (class "Default")
      (node (ref "P1") (pin "14") (pinfunction "RAM_SCK_14") (pintype "passive"))
    )
    (net (code "85") (name "unconnected-(P1A-RUN-Pad11)") (class "Default")
      (node (ref "P1") (pin "11") (pinfunction "RUN_11") (pintype "passive"))
    )
    (net (code "86") (name "unconnected-(P1A-SD_DET-Pad12)") (class "Default")
      (node (ref "P1") (pin "12") (pinfunction "SD_DET_12") (pintype "passive"))
    )
    (net (code "87") (name "unconnected-(P1A-SPI0_CS-Pad19)") (class "Default")
      (node (ref "P1") (pin "19") (pinfunction "SPI0_CS_19") (pintype "passive"))
    )
    (net (code "88") (name "unconnected-(P1A-SPI0_RX-Pad20)") (class "Default")
      (node (ref "P1") (pin "20") (pinfunction "SPI0_RX_20") (pintype "passive"))
    )
    (net (code "89") (name "unconnected-(P1A-SPI0_SCK-Pad17)") (class "Default")
      (node (ref "P1") (pin "17") (pinfunction "SPI0_SCK_17") (pintype "passive"))
    )
    (net (code "90") (name "unconnected-(P1A-SPI0_TX-Pad16)") (class "Default")
      (node (ref "P1") (pin "16") (pinfunction "SPI0_TX_16") (pintype "passive"))
    )
    (net (code "91") (name "unconnected-(P1B-RAM_IO2-Pad26)") (class "Default")
      (node (ref "P1") (pin "26") (pinfunction "RAM_IO2_26") (pintype "passive"))
    )
    (net (code "92") (name "unconnected-(P1B-RAM_IO3-Pad27)") (class "Default")
      (node (ref "P1") (pin "27") (pinfunction "RAM_IO3_27") (pintype "passive"))
    )
    (net (code "93") (name "unconnected-(P1B-RAM_RX-Pad25)") (class "Default")
      (node (ref "P1") (pin "25") (pinfunction "RAM_RX_25") (pintype "passive"))
    )
    (net (code "94") (name "unconnected-(P1B-RAM_TX-Pad24)") (class "Default")
      (node (ref "P1") (pin "24") (pinfunction "RAM_TX_24") (pintype "passive"))
    )
    (net (code "95") (name "unconnected-(P2-IM0-Pad8)") (class "Default")
      (node (ref "P2") (pin "8") (pinfunction "IM0_8") (pintype "passive+no_connect"))
    )
    (net (code "96") (name "unconnected-(P2-IM1-Pad7)") (class "Default")
      (node (ref "P2") (pin "7") (pinfunction "IM1_7") (pintype "passive+no_connect"))
    )
    (net (code "97") (name "unconnected-(P3-D2N-Pad20)") (class "Default")
      (node (ref "P3") (pin "20") (pinfunction "D2N_20") (pintype "passive+no_connect"))
    )
    (net (code "98") (name "unconnected-(P3-D2P-Pad19)") (class "Default")
      (node (ref "P3") (pin "19") (pinfunction "D2P_19") (pintype "passive+no_connect"))
    )
    (net (code "99") (name "unconnected-(P3-D3N-Pad23)") (class "Default")
      (node (ref "P3") (pin "23") (pinfunction "D3N_23") (pintype "passive+no_connect"))
    )
    (net (code "100") (name "unconnected-(P3-D3P-Pad22)") (class "Default")
      (node (ref "P3") (pin "22") (pinfunction "D3P_22") (pintype "passive+no_connect"))
    )
    (net (code "101") (name "unconnected-(P3-TE-Pad7)") (class "Default")
      (node (ref "P3") (pin "7") (pinfunction "TE_7") (pintype "passive+no_connect"))
    )
    (net (code "102") (name "unconnected-(U1A-RMII0_CLK-Pad29)") (class "Default")
      (node (ref "U1") (pin "29") (pinfunction "RMII0_CLK_29") (pintype "passive"))
    )
    (net (code "103") (name "unconnected-(U1A-RMII0_MDC-Pad25)") (class "Default")
      (node (ref "U1") (pin "25") (pinfunction "RMII0_MDC_25") (pintype "passive"))
    )
    (net (code "104") (name "unconnected-(U1A-RMII0_MDIO-Pad24)") (class "Default")
      (node (ref "U1") (pin "24") (pinfunction "RMII0_MDIO_24") (pintype "passive"))
    )
    (net (code "105") (name "unconnected-(U1A-RMII0_RXD0-Pad31)") (class "Default")
      (node (ref "U1") (pin "31") (pinfunction "RMII0_RXD0_31") (pintype "passive"))
    )
    (net (code "106") (name "unconnected-(U1A-RMII0_RXD1-Pad30)") (class "Default")
      (node (ref "U1") (pin "30") (pinfunction "RMII0_RXD1_30") (pintype "passive"))
    )
    (net (code "107") (name "unconnected-(U1A-RMII0_RXDV_CRS-Pad23)") (class "Default")
      (node (ref "U1") (pin "23") (pinfunction "RMII0_RXDV_CRS_23") (pintype "passive"))
    )
    (net (code "108") (name "unconnected-(U1A-RMII0_TXD0-Pad28)") (class "Default")
      (node (ref "U1") (pin "28") (pinfunction "RMII0_TXD0_28") (pintype "passive"))
    )
    (net (code "109") (name "unconnected-(U1A-RMII0_TXD1-Pad27)") (class "Default")
      (node (ref "U1") (pin "27") (pinfunction "RMII0_TXD1_27") (pintype "passive"))
    )
    (net (code "110") (name "unconnected-(U1A-RMII0_TXEN-Pad26)") (class "Default")
      (node (ref "U1") (pin "26") (pinfunction "RMII0_TXEN_26") (pintype "passive"))
    )
    (net (code "111") (name "unconnected-(U1A-RMII1_CLK-Pad19)") (class "Default")
      (node (ref "U1") (pin "19") (pinfunction "RMII1_CLK_19") (pintype "passive"))
    )
    (net (code "112") (name "unconnected-(U1A-RMII1_MDC-Pad15)") (class "Default")
      (node (ref "U1") (pin "15") (pinfunction "RMII1_MDC_15") (pintype "passive"))
    )
    (net (code "113") (name "unconnected-(U1A-RMII1_MDIO-Pad14)") (class "Default")
      (node (ref "U1") (pin "14") (pinfunction "RMII1_MDIO_14") (pintype "passive"))
    )
    (net (code "114") (name "unconnected-(U1A-RMII1_RXD0-Pad21)") (class "Default")
      (node (ref "U1") (pin "21") (pinfunction "RMII1_RXD0_21") (pintype "passive"))
    )
    (net (code "115") (name "unconnected-(U1A-RMII1_RXD1-Pad20)") (class "Default")
      (node (ref "U1") (pin "20") (pinfunction "RMII1_RXD1_20") (pintype "passive"))
    )
    (net (code "116") (name "unconnected-(U1A-RMII1_RXDV_CRS-Pad13)") (class "Default")
      (node (ref "U1") (pin "13") (pinfunction "RMII1_RXDV_CRS_13") (pintype "passive"))
    )
    (net (code "117") (name "unconnected-(U1A-RMII1_TXD0-Pad18)") (class "Default")
      (node (ref "U1") (pin "18") (pinfunction "RMII1_TXD0_18") (pintype "passive"))
    )
    (net (code "118") (name "unconnected-(U1A-RMII1_TXD1-Pad17)") (class "Default")
      (node (ref "U1") (pin "17") (pinfunction "RMII1_TXD1_17") (pintype "passive"))
    )
    (net (code "119") (name "unconnected-(U1A-RMII1_TXEN-Pad16)") (class "Default")
      (node (ref "U1") (pin "16") (pinfunction "RMII1_TXEN_16") (pintype "passive"))
    )
    (net (code "120") (name "unconnected-(U1B-ACODEC_ADC_INN-Pad53)") (class "Default")
      (node (ref "U1") (pin "53") (pinfunction "ACODEC_ADC_INN_53") (pintype "passive"))
    )
    (net (code "121") (name "unconnected-(U1B-ACODEC_ADC_INP-Pad52)") (class "Default")
      (node (ref "U1") (pin "52") (pinfunction "ACODEC_ADC_INP_52") (pintype "passive"))
    )
    (net (code "122") (name "unconnected-(U1B-GPIO0_D0_d-Pad51)") (class "Default")
      (node (ref "U1") (pin "51") (pinfunction "GPIO0_D0_d_51") (pintype "passive"))
    )
    (net (code "123") (name "unconnected-(U1B-NC-Pad40)") (class "Default")
      (node (ref "U1") (pin "40") (pinfunction "NC_40") (pintype "passive"))
    )
    (net (code "124") (name "unconnected-(U1B-NC-Pad41)") (class "Default")
      (node (ref "U1") (pin "41") (pinfunction "NC_41") (pintype "passive"))
    )
    (net (code "125") (name "unconnected-(U1B-NC-Pad42)") (class "Default")
      (node (ref "U1") (pin "42") (pinfunction "NC_42") (pintype "passive"))
    )
    (net (code "126") (name "unconnected-(U1B-NC-Pad43)") (class "Default")
      (node (ref "U1") (pin "43") (pinfunction "NC_43") (pintype "passive"))
    )
    (net (code "127") (name "unconnected-(U1B-NC-Pad44)") (class "Default")
      (node (ref "U1") (pin "44") (pinfunction "NC_44") (pintype "passive"))
    )
    (net (code "128") (name "unconnected-(U1B-NC-Pad45)") (class "Default")
      (node (ref "U1") (pin "45") (pinfunction "NC_45") (pintype "passive"))
    )
    (net (code "129") (name "unconnected-(U1B-NC-Pad57)") (class "Default")
      (node (ref "U1") (pin "57") (pinfunction "NC_57") (pintype "passive"))
    )
    (net (code "130") (name "unconnected-(U1B-NC-Pad58)") (class "Default")
      (node (ref "U1") (pin "58") (pinfunction "NC_58") (pintype "passive"))
    )
    (net (code "131") (name "unconnected-(U1B-NPOR_L-Pad46)") (class "Default")
      (node (ref "U1") (pin "46") (pinfunction "NPOR_L_46") (pintype "passive"))
    )
    (net (code "132") (name "unconnected-(U1B-SARADC_IN2-Pad49)") (class "Default")
      (node (ref "U1") (pin "49") (pinfunction "SARADC_IN2_49") (pintype "passive"))
    )
    (net (code "133") (name "unconnected-(U1B-SARADC_IN3-Pad50)") (class "Default")
      (node (ref "U1") (pin "50") (pinfunction "SARADC_IN3_50") (pintype "passive"))
    )
    (net (code "134") (name "unconnected-(U1B-USB20_OTG1_DM-Pad61)") (class "Default")
      (node (ref "U1") (pin "61") (pinfunction "USB20_OTG1_DM_61") (pintype "passive"))
    )
    (net (code "135") (name "unconnected-(U1B-USB20_OTG1_DP-Pad60)") (class "Default")
      (node (ref "U1") (pin "60") (pinfunction "USB20_OTG1_DP_60") (pintype "passive"))
    )
    (net (code "136") (name "unconnected-(U1C-VO_LCDC_D16-Pad83)") (class "Default")
      (node (ref "U1") (pin "83") (pinfunction "VO_LCDC_D16_83") (pintype "passive"))
    )
    (net (code "137") (name "unconnected-(U1D-CAN0_RX-Pad120)") (class "Default")
      (node (ref "U1") (pin "120") (pinfunction "CAN0_RX_120") (pintype "passive"))
    )
    (net (code "138") (name "unconnected-(U1D-CAN0_TX-Pad119)") (class "Default")
      (node (ref "U1") (pin "119") (pinfunction "CAN0_TX_119") (pintype "passive"))
    )
    (net (code "139") (name "unconnected-(U1D-CAN1_RX-Pad122)") (class "Default")
      (node (ref "U1") (pin "122") (pinfunction "CAN1_RX_122") (pintype "passive"))
    )
    (net (code "140") (name "unconnected-(U1D-CAN1_TX-Pad121)") (class "Default")
      (node (ref "U1") (pin "121") (pinfunction "CAN1_TX_121") (pintype "passive"))
    )
    (net (code "141") (name "unconnected-(U1D-SAI1_SCLK-Pad106)") (class "Default")
      (node (ref "U1") (pin "106") (pinfunction "SAI1_SCLK_106") (pintype "passive"))
    )
    (net (code "142") (name "unconnected-(U1D-SAI1_SDI-Pad108)") (class "Default")
      (node (ref "U1") (pin "108") (pinfunction "SAI1_SDI_108") (pintype "passive"))
    )
    (net (code "143") (name "unconnected-(U1D-SAI1_SDO0-Pad109)") (class "Default")
      (node (ref "U1") (pin "109") (pinfunction "SAI1_SDO0_109") (pintype "passive"))
    )
    (net (code "144") (name "unconnected-(U1D-UART3_RX-Pad118)") (class "Default")
      (node (ref "U1") (pin "118") (pinfunction "UART3_RX_118") (pintype "passive"))
    )
    (net (code "145") (name "unconnected-(U1D-UART3_TX-Pad117)") (class "Default")
      (node (ref "U1") (pin "117") (pinfunction "UART3_TX_117") (pintype "passive"))
    )
    (net (code "146") (name "unconnected-(U6-RST-Pad4)") (class "Default")
      (node (ref "U6") (pin "4") (pinfunction "RST_4") (pintype "passive+no_connect"))
    )
  )
)
